# PreAmp.net
KiCad netlist of a schematic drawn in Altium Designer
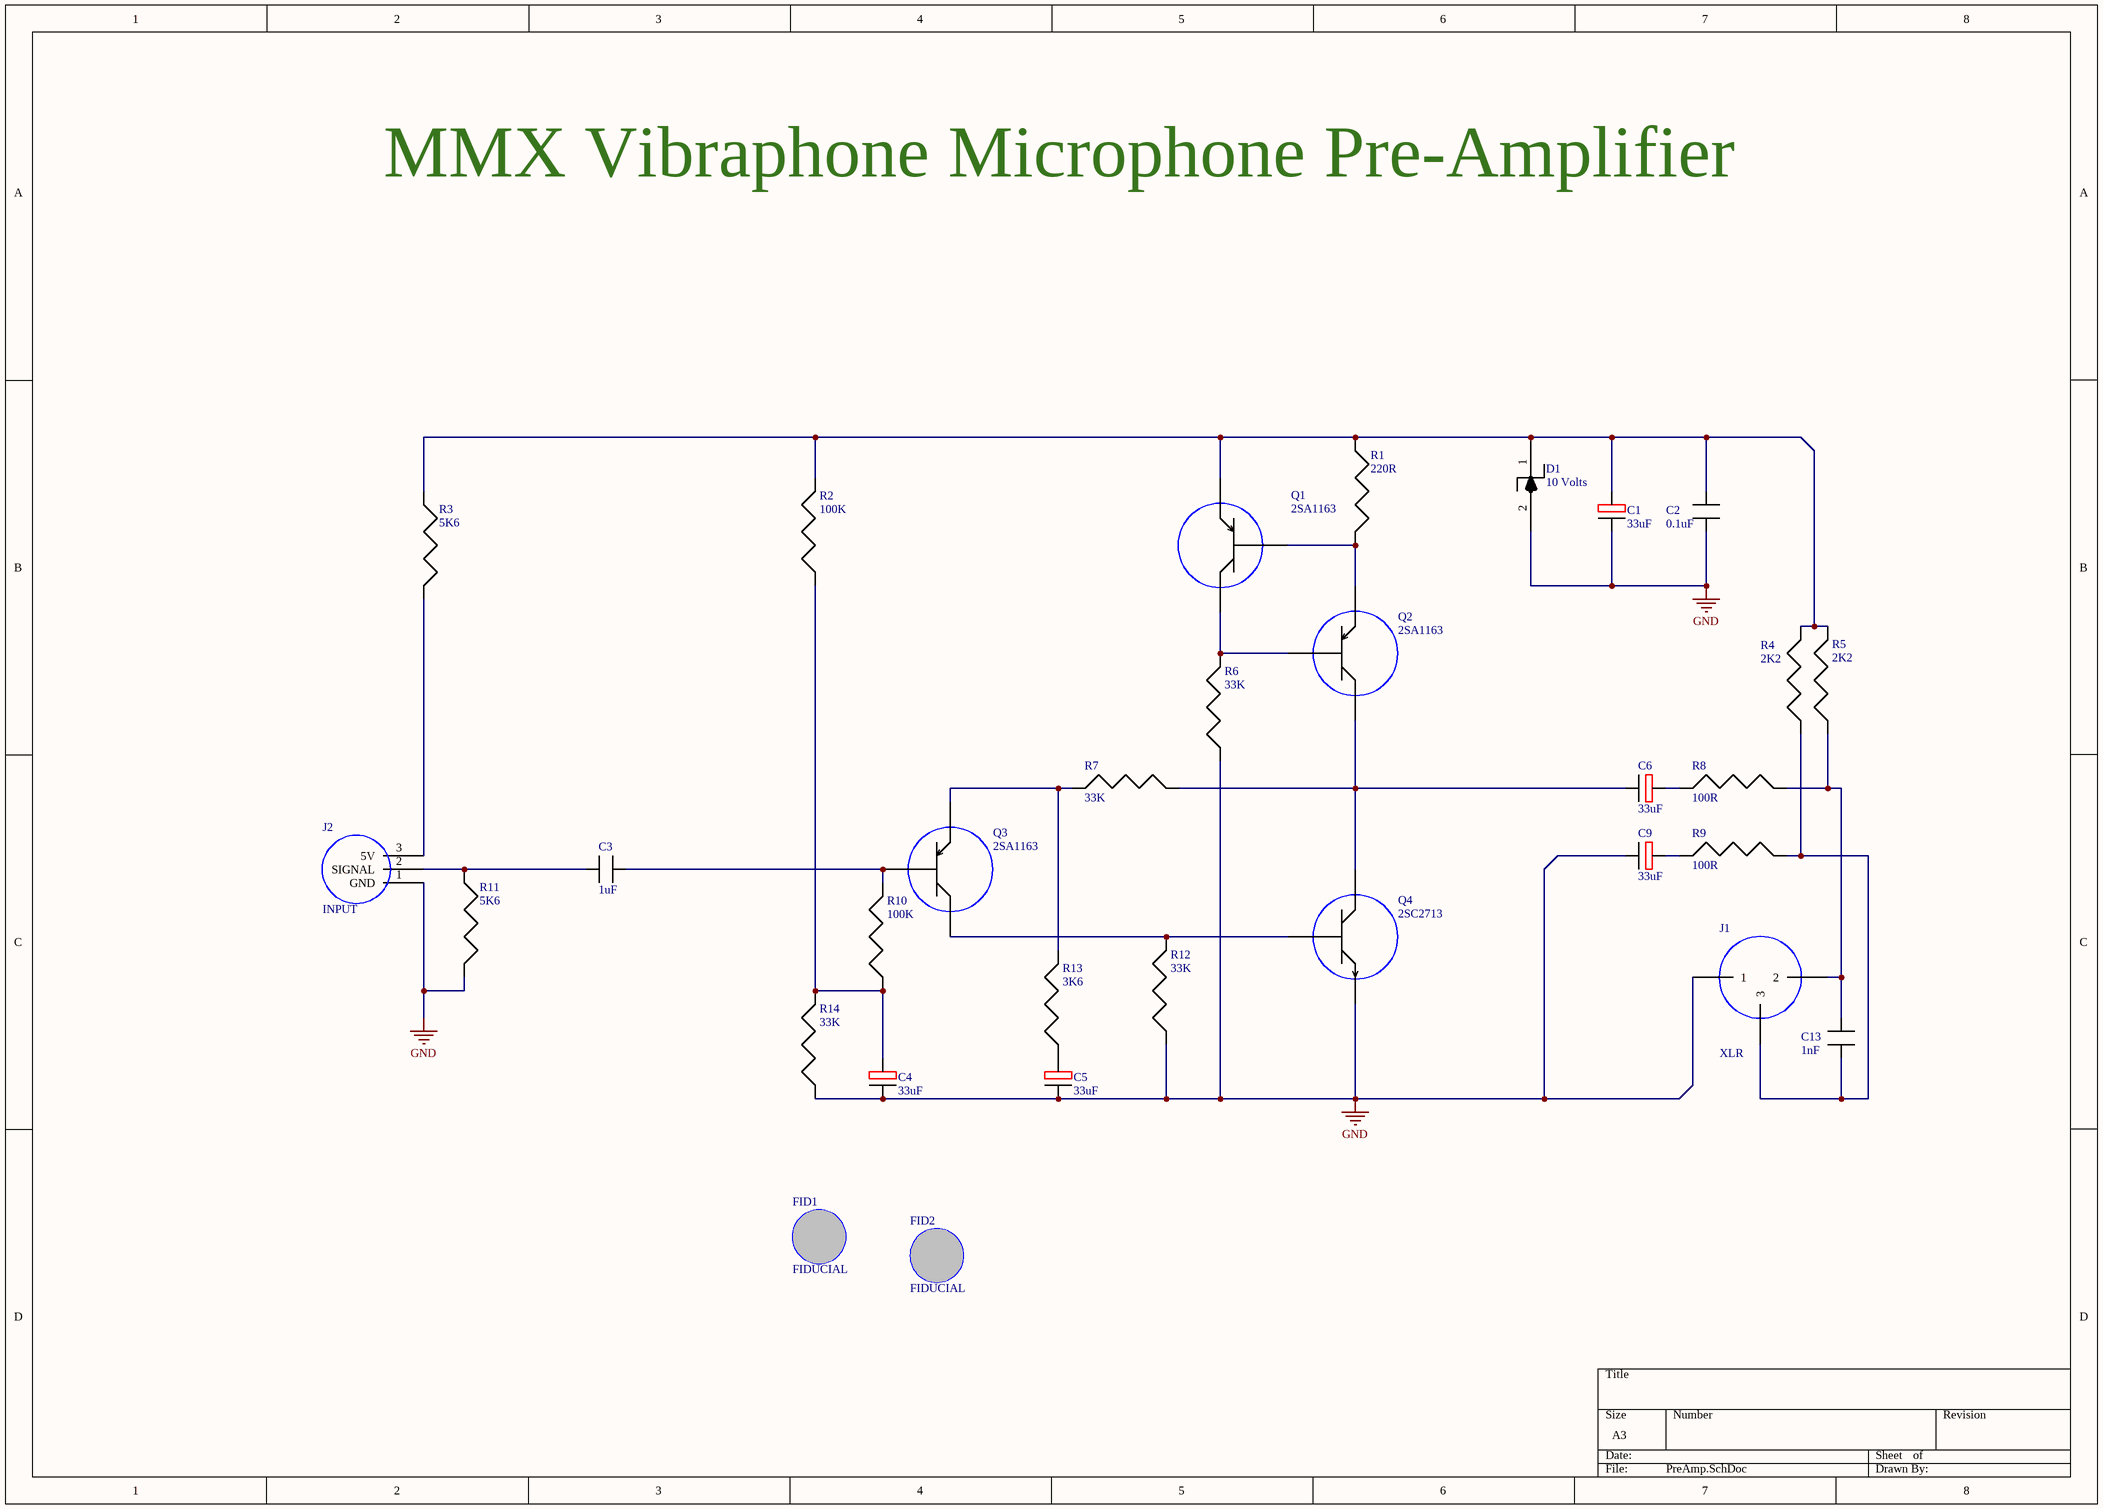
[diagram p0: PreAmp.SchDoc]

(export (version "E")
  (design (tool "Eeschema 10.0.6"))
  (components
    (comp (ref "C1") (value "33uF") (footprint "UFW1J330MED") (libsource (lib "MicLib") (part "CE")))
    (comp (ref "C2") (value "0.1uF") (footprint "C0805") (libsource (lib "MicLib") (part "C")))
    (comp (ref "C3") (value "1uF") (footprint "C1210") (libsource (lib "MicLib") (part "C")))
    (comp (ref "C4") (value "33uF") (footprint "UFW1J330MED") (libsource (lib "MicLib") (part "CE")))
    (comp (ref "C5") (value "33uF") (footprint "UFW1J330MED") (libsource (lib "MicLib") (part "CE")))
    (comp (ref "C6") (value "33uF") (footprint "UFW1J330MED") (libsource (lib "") (part "CE_1")))
    (comp (ref "C9") (value "33uF") (footprint "UFW1J330MED") (libsource (lib "") (part "CE_1")))
    (comp (ref "C13") (value "1nF") (footprint "C0805") (libsource (lib "MicLib") (part "C")))
    (comp (ref "D1") (value "10 Volts") (footprint "SOD80C") (libsource (lib "MicLib") (part "BZV55B10")))
    (comp (ref "FID1") (value "FIDUCIAL") (footprint "FIDUCIAL") (libsource (lib "MicLib") (part "FIDUCIAL")))
    (comp (ref "FID2") (value "FIDUCIAL") (footprint "FIDUCIAL") (libsource (lib "MicLib") (part "FIDUCIAL")))
    (comp (ref "J1") (value "XLR") (footprint "XLR") (libsource (lib "MicLib") (part "XLR")))
    (comp (ref "J2") (value "INPUT") (footprint "INPUT") (libsource (lib "MicLib") (part "INPUT")))
    (comp (ref "Q1")
      (value "2SA1163")
      (footprint "TO-236/SC-59/SOT-23")
      (libsource (lib "MicLib") (part "PNP"))
    )
    (comp (ref "Q2")
      (value "2SA1163")
      (footprint "TO-236/SC-59/SOT-23")
      (libsource (lib "MicLib") (part "PNP"))
    )
    (comp (ref "Q3")
      (value "2SA1163")
      (footprint "TO-236/SC-59/SOT-23")
      (libsource (lib "MicLib") (part "PNP"))
    )
    (comp (ref "Q4")
      (value "2SC2713")
      (footprint "TO-236/SC-59/SOT-23")
      (libsource (lib "MicLib") (part "NPN"))
    )
    (comp (ref "R1") (value "220R") (footprint "MMA0204") (libsource (lib "MicLib") (part "Resistor")))
    (comp (ref "R2") (value "100K") (footprint "MMA0204") (libsource (lib "MicLib") (part "Resistor")))
    (comp (ref "R3") (value "5K6") (footprint "MMA0204") (libsource (lib "MicLib") (part "Resistor")))
    (comp (ref "R4") (value "2K2") (footprint "MMA0204") (libsource (lib "MicLib") (part "Resistor")))
    (comp (ref "R5") (value "2K2") (footprint "MMA0204") (libsource (lib "MicLib") (part "Resistor")))
    (comp (ref "R6") (value "33K") (footprint "MMA0204") (libsource (lib "MicLib") (part "Resistor")))
    (comp (ref "R7") (value "33K") (footprint "MMA0204") (libsource (lib "MicLib") (part "Resistor")))
    (comp (ref "R8") (value "100R") (footprint "MMA0204") (libsource (lib "MicLib") (part "Resistor")))
    (comp (ref "R9") (value "100R") (footprint "MMA0204") (libsource (lib "MicLib") (part "Resistor")))
    (comp (ref "R10") (value "100K") (footprint "MMA0204") (libsource (lib "MicLib") (part "Resistor")))
    (comp (ref "R11") (value "5K6") (footprint "MMA0204") (libsource (lib "MicLib") (part "Resistor")))
    (comp (ref "R12") (value "33K") (footprint "MMA0204") (libsource (lib "MicLib") (part "Resistor")))
    (comp (ref "R13") (value "3K6") (footprint "MMA0204") (libsource (lib "MicLib") (part "Resistor")))
    (comp (ref "R14") (value "33K") (footprint "MMA0204") (libsource (lib "MicLib") (part "Resistor")))
  )
  (nets
    (net (code "1") (name "GND") (class "Default")
      (node (ref "C1") (pin "2") (pinfunction "-_2") (pintype "passive"))
      (node (ref "C2") (pin "2") (pinfunction "2_2") (pintype "passive"))
      (node (ref "C4") (pin "2") (pinfunction "-_2") (pintype "passive"))
      (node (ref "C5") (pin "2") (pinfunction "-_2") (pintype "passive"))
      (node (ref "C9") (pin "2") (pinfunction "-_2") (pintype "passive"))
      (node (ref "D1") (pin "2") (pinfunction "A_2") (pintype "passive"))
      (node (ref "J1") (pin "1") (pinfunction "1_1") (pintype "passive"))
      (node (ref "J2") (pin "1") (pinfunction "GND_1") (pintype "passive"))
      (node (ref "Q4") (pin "2") (pinfunction "E_2") (pintype "passive"))
      (node (ref "R11") (pin "2") (pinfunction "2_2") (pintype "passive"))
      (node (ref "R12") (pin "1") (pinfunction "1_1") (pintype "passive"))
      (node (ref "R14") (pin "1") (pinfunction "1_1") (pintype "passive"))
      (node (ref "R6") (pin "1") (pinfunction "1_1") (pintype "passive"))
    )
    (net (code "2") (name "Net-(C1-+)") (class "Default")
      (node (ref "C1") (pin "1") (pinfunction "+_1") (pintype "passive"))
      (node (ref "C2") (pin "1") (pinfunction "1_1") (pintype "passive"))
      (node (ref "D1") (pin "1") (pinfunction "K_1") (pintype "passive"))
      (node (ref "Q1") (pin "2") (pinfunction "E_2") (pintype "passive"))
      (node (ref "R1") (pin "1") (pinfunction "1_1") (pintype "passive"))
      (node (ref "R2") (pin "2") (pinfunction "2_2") (pintype "passive"))
      (node (ref "R3") (pin "1") (pinfunction "1_1") (pintype "passive"))
      (node (ref "R4") (pin "2") (pinfunction "2_2") (pintype "passive"))
      (node (ref "R5") (pin "2") (pinfunction "2_2") (pintype "passive"))
    )
    (net (code "3") (name "Net-(C4-+)") (class "Default")
      (node (ref "C4") (pin "1") (pinfunction "+_1") (pintype "passive"))
      (node (ref "R10") (pin "1") (pinfunction "1_1") (pintype "passive"))
      (node (ref "R14") (pin "2") (pinfunction "2_2") (pintype "passive"))
      (node (ref "R2") (pin "1") (pinfunction "1_1") (pintype "passive"))
    )
    (net (code "4") (name "Net-(C5-+)") (class "Default")
      (node (ref "C5") (pin "1") (pinfunction "+_1") (pintype "passive"))
      (node (ref "R13") (pin "1") (pinfunction "1_1") (pintype "passive"))
    )
    (net (code "5") (name "Net-(C6-+)") (class "Default")
      (node (ref "C6") (pin "1") (pinfunction "+_1") (pintype "passive"))
      (node (ref "R8") (pin "1") (pinfunction "1_1") (pintype "passive"))
    )
    (net (code "6") (name "Net-(C6--)") (class "Default")
      (node (ref "C6") (pin "2") (pinfunction "-_2") (pintype "passive"))
      (node (ref "Q2") (pin "3") (pinfunction "C_3") (pintype "passive"))
      (node (ref "Q4") (pin "3") (pinfunction "C_3") (pintype "passive"))
      (node (ref "R7") (pin "2") (pinfunction "2_2") (pintype "passive"))
    )
    (net (code "7") (name "Net-(C9-+)") (class "Default")
      (node (ref "C9") (pin "1") (pinfunction "+_1") (pintype "passive"))
      (node (ref "R9") (pin "1") (pinfunction "1_1") (pintype "passive"))
    )
    (net (code "8") (name "Net-(C13-Pad1)") (class "Default")
      (node (ref "C13") (pin "1") (pinfunction "1_1") (pintype "passive"))
      (node (ref "J1") (pin "2") (pinfunction "2_2") (pintype "passive"))
      (node (ref "R5") (pin "1") (pinfunction "1_1") (pintype "passive"))
      (node (ref "R8") (pin "2") (pinfunction "2_2") (pintype "passive"))
    )
    (net (code "9") (name "Net-(C13-Pad2)") (class "Default")
      (node (ref "C13") (pin "2") (pinfunction "2_2") (pintype "passive"))
      (node (ref "J1") (pin "3") (pinfunction "3_3") (pintype "passive"))
      (node (ref "R4") (pin "1") (pinfunction "1_1") (pintype "passive"))
      (node (ref "R9") (pin "2") (pinfunction "2_2") (pintype "passive"))
    )
    (net (code "10") (name "Net-(J2-5V)") (class "Default")
      (node (ref "J2") (pin "3") (pinfunction "5V_3") (pintype "passive"))
      (node (ref "R3") (pin "2") (pinfunction "2_2") (pintype "passive"))
    )
    (net (code "11") (name "Net-(J2-SIGNAL)") (class "Default")
      (node (ref "C3") (pin "1") (pinfunction "1_1") (pintype "passive"))
      (node (ref "J2") (pin "2") (pinfunction "SIGNAL_2") (pintype "passive"))
      (node (ref "R11") (pin "1") (pinfunction "1_1") (pintype "passive"))
    )
    (net (code "12") (name "Net-(Q1-B)") (class "Default")
      (node (ref "Q1") (pin "1") (pinfunction "B_1") (pintype "passive"))
      (node (ref "Q2") (pin "2") (pinfunction "E_2") (pintype "passive"))
      (node (ref "R1") (pin "2") (pinfunction "2_2") (pintype "passive"))
    )
    (net (code "13") (name "Net-(Q1-C)") (class "Default")
      (node (ref "Q1") (pin "3") (pinfunction "C_3") (pintype "passive"))
      (node (ref "Q2") (pin "1") (pinfunction "B_1") (pintype "passive"))
      (node (ref "R6") (pin "2") (pinfunction "2_2") (pintype "passive"))
    )
    (net (code "14") (name "Net-(Q3-B)") (class "Default")
      (node (ref "C3") (pin "2") (pinfunction "2_2") (pintype "passive"))
      (node (ref "Q3") (pin "1") (pinfunction "B_1") (pintype "passive"))
      (node (ref "R10") (pin "2") (pinfunction "2_2") (pintype "passive"))
    )
    (net (code "15") (name "Net-(Q3-C)") (class "Default")
      (node (ref "Q3") (pin "3") (pinfunction "C_3") (pintype "passive"))
      (node (ref "Q4") (pin "1") (pinfunction "B_1") (pintype "passive"))
      (node (ref "R12") (pin "2") (pinfunction "2_2") (pintype "passive"))
    )
    (net (code "16") (name "Net-(Q3-E)") (class "Default")
      (node (ref "Q3") (pin "2") (pinfunction "E_2") (pintype "passive"))
      (node (ref "R13") (pin "2") (pinfunction "2_2") (pintype "passive"))
      (node (ref "R7") (pin "1") (pinfunction "1_1") (pintype "passive"))
    )
  )
)
